# LED_bar.net
KiCad netlist of a schematic drawn in EAGLE
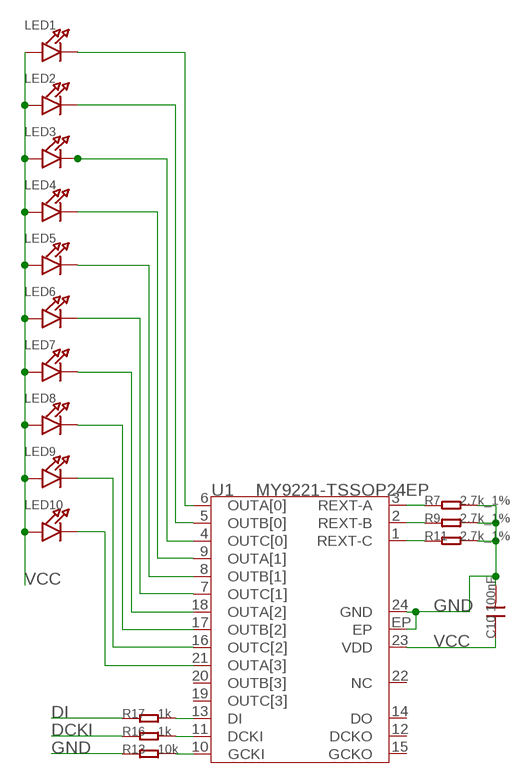
[diagram p0: schematic, sheet 1]

(export (version "E")
  (design (tool "Eeschema 10.0.6"))
  (components
    (comp (ref "C10")
      (value "100nF")
      (footprint "eagle-import:0603")
      (libsource (lib "eagle-import") (part "C-0603"))
    )
    (comp (ref "LED1")
      (value "LED0805")
      (footprint "eagle-import:CHIPLED_0805")
      (libsource (lib "eagle-import") (part "LED0805"))
    )
    (comp (ref "LED2")
      (value "LED0805")
      (footprint "eagle-import:CHIPLED_0805")
      (libsource (lib "eagle-import") (part "LED0805"))
    )
    (comp (ref "LED3")
      (value "LED0805")
      (footprint "eagle-import:CHIPLED_0805")
      (libsource (lib "eagle-import") (part "LED0805"))
    )
    (comp (ref "LED4")
      (value "LED0805")
      (footprint "eagle-import:CHIPLED_0805")
      (libsource (lib "eagle-import") (part "LED0805"))
    )
    (comp (ref "LED5")
      (value "LED0805")
      (footprint "eagle-import:CHIPLED_0805")
      (libsource (lib "eagle-import") (part "LED0805"))
    )
    (comp (ref "LED6")
      (value "LED0805")
      (footprint "eagle-import:CHIPLED_0805")
      (libsource (lib "eagle-import") (part "LED0805"))
    )
    (comp (ref "LED7")
      (value "LED0805")
      (footprint "eagle-import:CHIPLED_0805")
      (libsource (lib "eagle-import") (part "LED0805"))
    )
    (comp (ref "LED8")
      (value "LED0805")
      (footprint "eagle-import:CHIPLED_0805")
      (libsource (lib "eagle-import") (part "LED0805"))
    )
    (comp (ref "LED9")
      (value "LED0805")
      (footprint "eagle-import:CHIPLED_0805")
      (libsource (lib "eagle-import") (part "LED0805"))
    )
    (comp (ref "LED10")
      (value "LED0805")
      (footprint "eagle-import:CHIPLED_0805")
      (libsource (lib "eagle-import") (part "LED0805"))
    )
    (comp (ref "R7")
      (value "2.7k_1%")
      (footprint "eagle-import:0603")
      (libsource (lib "eagle-import") (part "R-0603"))
    )
    (comp (ref "R9")
      (value "2.7k_1%")
      (footprint "eagle-import:0603")
      (libsource (lib "eagle-import") (part "R-0603"))
    )
    (comp (ref "R11")
      (value "2.7k_1%")
      (footprint "eagle-import:0603")
      (libsource (lib "eagle-import") (part "R-0603"))
    )
    (comp (ref "R13")
      (value "10k")
      (footprint "eagle-import:0603")
      (libsource (lib "eagle-import") (part "R-0603"))
    )
    (comp (ref "R16")
      (value "1k")
      (footprint "eagle-import:0603")
      (libsource (lib "eagle-import") (part "R-0603"))
    )
    (comp (ref "R17")
      (value "1k")
      (footprint "eagle-import:0603")
      (libsource (lib "eagle-import") (part "R-0603"))
    )
    (comp (ref "U1")
      (value "MY9221-TSSOP24EP")
      (footprint "eagle-import:TSSOP24EP")
      (libsource (lib "eagle-import") (part "MY9221-TSSOP24EP"))
    )
  )
  (nets
    (net (code "1") (name "/DCKI") (class "Default")
      (node (ref "R16") (pin "1") (pinfunction "1_1") (pintype "passive"))
    )
    (net (code "2") (name "/DI") (class "Default")
      (node (ref "R17") (pin "1") (pinfunction "1_1") (pintype "passive"))
    )
    (net (code "3") (name "/GND") (class "Default")
      (node (ref "C10") (pin "2") (pinfunction "2_2") (pintype "passive"))
      (node (ref "R11") (pin "2") (pinfunction "2_2") (pintype "passive"))
      (node (ref "R13") (pin "1") (pinfunction "1_1") (pintype "passive"))
      (node (ref "R7") (pin "2") (pinfunction "2_2") (pintype "passive"))
      (node (ref "R9") (pin "2") (pinfunction "2_2") (pintype "passive"))
      (node (ref "U1") (pin "24") (pinfunction "GND_24") (pintype "power_in"))
      (node (ref "U1") (pin "EP") (pinfunction "EP_EP") (pintype "bidirectional"))
    )
    (net (code "4") (name "/VCC") (class "Default")
      (node (ref "C10") (pin "1") (pinfunction "1_1") (pintype "passive"))
      (node (ref "LED1") (pin "A") (pinfunction "A_A") (pintype "passive"))
      (node (ref "LED10") (pin "A") (pinfunction "A_A") (pintype "passive"))
      (node (ref "LED2") (pin "A") (pinfunction "A_A") (pintype "passive"))
      (node (ref "LED3") (pin "A") (pinfunction "A_A") (pintype "passive"))
      (node (ref "LED4") (pin "A") (pinfunction "A_A") (pintype "passive"))
      (node (ref "LED5") (pin "A") (pinfunction "A_A") (pintype "passive"))
      (node (ref "LED6") (pin "A") (pinfunction "A_A") (pintype "passive"))
      (node (ref "LED7") (pin "A") (pinfunction "A_A") (pintype "passive"))
      (node (ref "LED8") (pin "A") (pinfunction "A_A") (pintype "passive"))
      (node (ref "LED9") (pin "A") (pinfunction "A_A") (pintype "passive"))
      (node (ref "U1") (pin "23") (pinfunction "VDD_23") (pintype "power_in"))
    )
    (net (code "5") (name "Net-(U1-DCKI)") (class "Default")
      (node (ref "R16") (pin "2") (pinfunction "2_2") (pintype "passive"))
      (node (ref "U1") (pin "11") (pinfunction "DCKI_11") (pintype "bidirectional"))
    )
    (net (code "6") (name "Net-(U1-DI)") (class "Default")
      (node (ref "R17") (pin "2") (pinfunction "2_2") (pintype "passive"))
      (node (ref "U1") (pin "13") (pinfunction "DI_13") (pintype "bidirectional"))
    )
    (net (code "7") (name "Net-(U1-GCKI)") (class "Default")
      (node (ref "R13") (pin "2") (pinfunction "2_2") (pintype "passive"))
      (node (ref "U1") (pin "10") (pinfunction "GCKI_10") (pintype "bidirectional"))
    )
    (net (code "8") (name "Net-(U1-OUTA[0])") (class "Default")
      (node (ref "LED1") (pin "C") (pinfunction "C_C") (pintype "passive"))
      (node (ref "U1") (pin "6") (pinfunction "OUTA[0]_6") (pintype "bidirectional"))
    )
    (net (code "9") (name "Net-(U1-OUTA[1])") (class "Default")
      (node (ref "LED4") (pin "C") (pinfunction "C_C") (pintype "passive"))
      (node (ref "U1") (pin "9") (pinfunction "OUTA[1]_9") (pintype "bidirectional"))
    )
    (net (code "10") (name "Net-(U1-OUTA[2])") (class "Default")
      (node (ref "LED7") (pin "C") (pinfunction "C_C") (pintype "passive"))
      (node (ref "U1") (pin "18") (pinfunction "OUTA[2]_18") (pintype "bidirectional"))
    )
    (net (code "11") (name "Net-(U1-OUTA[3])") (class "Default")
      (node (ref "LED10") (pin "C") (pinfunction "C_C") (pintype "passive"))
      (node (ref "U1") (pin "21") (pinfunction "OUTA[3]_21") (pintype "bidirectional"))
    )
    (net (code "12") (name "Net-(U1-OUTB[0])") (class "Default")
      (node (ref "LED2") (pin "C") (pinfunction "C_C") (pintype "passive"))
      (node (ref "U1") (pin "5") (pinfunction "OUTB[0]_5") (pintype "bidirectional"))
    )
    (net (code "13") (name "Net-(U1-OUTB[1])") (class "Default")
      (node (ref "LED5") (pin "C") (pinfunction "C_C") (pintype "passive"))
      (node (ref "U1") (pin "8") (pinfunction "OUTB[1]_8") (pintype "bidirectional"))
    )
    (net (code "14") (name "Net-(U1-OUTB[2])") (class "Default")
      (node (ref "LED8") (pin "C") (pinfunction "C_C") (pintype "passive"))
      (node (ref "U1") (pin "17") (pinfunction "OUTB[2]_17") (pintype "bidirectional"))
    )
    (net (code "15") (name "Net-(U1-OUTC[0])") (class "Default")
      (node (ref "LED3") (pin "C") (pinfunction "C_C") (pintype "passive"))
      (node (ref "U1") (pin "4") (pinfunction "OUTC[0]_4") (pintype "bidirectional"))
    )
    (net (code "16") (name "Net-(U1-OUTC[1])") (class "Default")
      (node (ref "LED6") (pin "C") (pinfunction "C_C") (pintype "passive"))
      (node (ref "U1") (pin "7") (pinfunction "OUTC[1]_7") (pintype "bidirectional"))
    )
    (net (code "17") (name "Net-(U1-OUTC[2])") (class "Default")
      (node (ref "LED9") (pin "C") (pinfunction "C_C") (pintype "passive"))
      (node (ref "U1") (pin "16") (pinfunction "OUTC[2]_16") (pintype "bidirectional"))
    )
    (net (code "18") (name "Net-(U1-REXT-A)") (class "Default")
      (node (ref "R7") (pin "1") (pinfunction "1_1") (pintype "passive"))
      (node (ref "U1") (pin "3") (pinfunction "REXT-A_3") (pintype "bidirectional"))
    )
    (net (code "19") (name "Net-(U1-REXT-B)") (class "Default")
      (node (ref "R9") (pin "1") (pinfunction "1_1") (pintype "passive"))
      (node (ref "U1") (pin "2") (pinfunction "REXT-B_2") (pintype "bidirectional"))
    )
    (net (code "20") (name "Net-(U1-REXT-C)") (class "Default")
      (node (ref "R11") (pin "1") (pinfunction "1_1") (pintype "passive"))
      (node (ref "U1") (pin "1") (pinfunction "REXT-C_1") (pintype "bidirectional"))
    )
    (net (code "21") (name "unconnected-(U1-DCKO-Pad12)") (class "Default")
      (node (ref "U1") (pin "12") (pinfunction "DCKO_12") (pintype "bidirectional"))
    )
    (net (code "22") (name "unconnected-(U1-DO-Pad14)") (class "Default")
      (node (ref "U1") (pin "14") (pinfunction "DO_14") (pintype "bidirectional"))
    )
    (net (code "23") (name "unconnected-(U1-GCKO-Pad15)") (class "Default")
      (node (ref "U1") (pin "15") (pinfunction "GCKO_15") (pintype "bidirectional"))
    )
    (net (code "24") (name "unconnected-(U1-NC-Pad22)") (class "Default")
      (node (ref "U1") (pin "22") (pinfunction "NC_22") (pintype "bidirectional"))
    )
    (net (code "25") (name "unconnected-(U1-OUTB[3]-Pad20)") (class "Default")
      (node (ref "U1") (pin "20") (pinfunction "OUTB[3]_20") (pintype "bidirectional"))
    )
    (net (code "26") (name "unconnected-(U1-OUTC[3]-Pad19)") (class "Default")
      (node (ref "U1") (pin "19") (pinfunction "OUTC[3]_19") (pintype "bidirectional"))
    )
  )
)
